# NGNIv1_32.net
KiCad netlist of a schematic drawn in Altium Designer
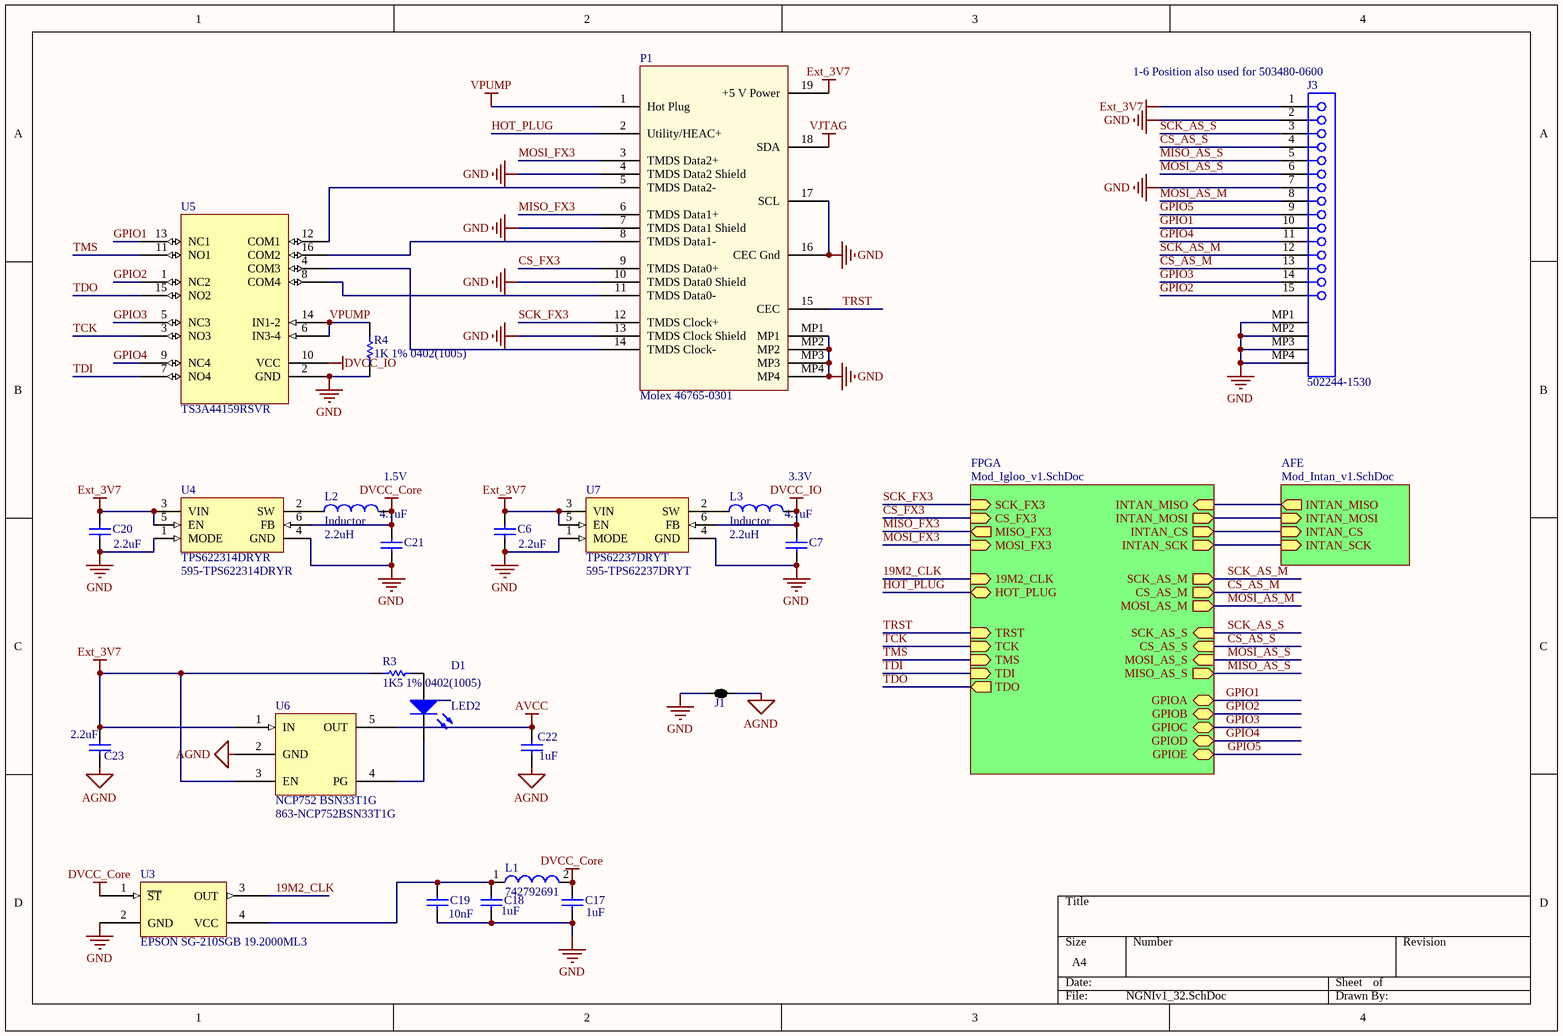
[diagram p0: NGNIv1_32.SchDoc]

(export (version "E")
  (design (tool "Eeschema 10.0.6"))
  (components
    (comp (ref "C6")
      (value "2.2uF")
      (footprint "CAPC0402(1005)60_L")
      (description "CAP 2.2uF 10V Â±20% 0402 (1005 Metric) Thickness 0.6mm SMD")
      (fields (field (name "TOLERANCE") "Â±20%") (field (name "Comment") "CAP 2.2uF 10V 0402(1005)"))
      (libsource (lib "Altium Content Vault") (part "CMP-1034-02128-1"))
    )
    (comp (ref "C7")
      (value "4.7uF")
      (footprint "CAPC0402(1005)60_N")
      (description "CAP 4.7uF 6.3V Â±20% 0402 (1005 Metric) Thickness 0.6mm SMD")
      (fields (field (name "TOLERANCE") "Â±20%") (field (name "Comment") "CAP 4.7uF 6.3V 0402(1005)"))
      (libsource (lib "Altium Content Vault") (part "CMP-1034-02137-1"))
    )
    (comp (ref "C17")
      (value "1uF")
      (footprint "CAPC0402(1005)60_L")
      (description "CAP 1uF 16V Â±10% 0402 (1005 Metric) Thickness 0.6mm SMD")
      (fields (field (name "TOLERANCE") "Â±10%") (field (name "Comment") "CAP 1uF 16V 0402(1005)"))
      (libsource (lib "Altium Content Vault") (part "CMP-1034-02119-1"))
    )
    (comp (ref "C18")
      (value "1uF")
      (footprint "CAPC0402(1005)60_L")
      (description "CAP 1uF 16V Â±20% 0402 (1005 Metric) Thickness 0.6mm SMD")
      (fields (field (name "TOLERANCE") "Â±20%") (field (name "Comment") "CAP 1uF 16V 0402(1005)"))
      (libsource (lib "Altium Content Vault") (part "CMP-1034-02120-1"))
    )
    (comp (ref "C19")
      (value "10nF")
      (footprint "CAPC0402(1005)60_L")
      (description "CAP 10nF 25V ±5% 0402 (1005 Metric) Thickness 0.6mm SMD")
      (fields (field (name "TOLERANCE") "±5%") (field (name "Comment") "CAP 10nF 25V 0402(1005)"))
      (libsource (lib "Altium Content Vault") (part "CMP-1034-01879-1"))
    )
    (comp (ref "C20")
      (value "2.2uF")
      (footprint "CAPC0402(1005)60_L")
      (description "CAP 2.2uF 10V Â±20% 0402 (1005 Metric) Thickness 0.6mm SMD")
      (fields (field (name "TOLERANCE") "Â±20%") (field (name "Comment") "CAP 2.2uF 10V 0402(1005)"))
      (libsource (lib "Altium Content Vault") (part "CMP-1034-02128-1"))
    )
    (comp (ref "C21")
      (value "4.7uF")
      (footprint "CAPC0402(1005)60_N")
      (description "CAP 4.7uF 6.3V Â±20% 0402 (1005 Metric) Thickness 0.6mm SMD")
      (fields (field (name "TOLERANCE") "Â±20%") (field (name "Comment") "CAP 4.7uF 6.3V 0402(1005)"))
      (libsource (lib "Altium Content Vault") (part "CMP-1034-02137-1"))
    )
    (comp (ref "C22")
      (value "1uF")
      (footprint "CAPC0402(1005)60_L")
      (description "CAP 1uF 16V ±10% 0402 (1005 Metric) Thickness 0.6mm SMD")
      (fields (field (name "TOLERANCE") "±10%") (field (name "Comment") "CAP 1uF 16V 0402(1005)"))
      (libsource (lib "Altium Content Vault") (part "CMP-1034-02119-1"))
    )
    (comp (ref "C23")
      (value "2.2uF")
      (footprint "CAPC0603(1608)100_L")
      (description "CAP 2.2uF 25V ±10% 0603 (1608 Metric) Thickness 1mm SMD")
      (fields (field (name "TOLERANCE") "±10%") (field (name "Comment") "CAP 2.2uF 25V 0603(1608)"))
      (libsource (lib "Altium Content Vault") (part "CMP-1035-02767-1"))
    )
    (comp (ref "D1")
      (value "LED2")
      (footprint "LED 0610")
      (description "Typical RED, GREEN, YELLOW, AMBER GaAs LED")
      (fields (field (name "PUBLISHER") "Altium Limited"))
      (libsource (lib "USBridge") (part "LED2"))
    )
    (comp (ref "J1")
      (value "2 way net tie junction")
      (footprint "2way_micro")
      (libsource (lib "NetTie") (part "2way"))
    )
    (comp (ref "J3")
      (value "502244-1530")
      (footprint "MOLX-502244-1530")
      (libsource (lib "USBridge") (part "MOLX-502244-1530"))
    )
    (comp (ref "L1")
      (value "742792691")
      (footprint "SMD-0603")
      (description "SMD EMI Suppression Ferrite Bead WE-CBF, Z = 1500 Ohm")
      (libsource (lib "Altium Content Vault") (part "PAS-IND-INDUCTOR-2"))
    )
    (comp (ref "L2")
      (value "Inductor")
      (footprint "2029")
      (description "LQM21PN2R2")
      (fields (field (name "ALTIUM_VALUE") "2.2uH") (field (name "PUBLISHER") "Altium Limited"))
      (libsource (lib "Miscellaneous Devices") (part "Inductor"))
    )
    (comp (ref "L3")
      (value "Inductor")
      (footprint "2029")
      (description "LQM21PN2R2")
      (fields (field (name "ALTIUM_VALUE") "2.2uH") (field (name "PUBLISHER") "Altium Limited"))
      (libsource (lib "Miscellaneous Devices") (part "Inductor"))
    )
    (comp (ref "P1")
      (value "Molex 46765-0301")
      (footprint "MOLEX 0467650301")
      (description "Micro HDMI")
      (libsource (lib "Schlib1") (part "Molex 46765-0301"))
    )
    (comp (ref "R3")
      (value "1K5 1% 0402(1005)")
      (footprint "RESC0402(1005)_L")
      (description "1K5 0.063W 1% 0402 (1005 Metric)  SMD")
      (fields (field (name "TOLERANCE") "1 %") (field (name "POWER") "0.063 W"))
      (libsource (lib "Altium Content Vault") (part "RES"))
    )
    (comp (ref "R4")
      (value "1K 1% 0402(1005)")
      (footprint "RESC0402(1005)_L")
      (description "1K 0.063W 1% 0402 (1005 Metric)  SMD")
      (fields (field (name "TOLERANCE") "1 %") (field (name "POWER") "0.063 W"))
      (libsource (lib "Altium Content Vault") (part "RES"))
    )
    (comp (ref "U3")
      (value "EPSON SG-210SGB 19.2000ML3")
      (footprint "SG-210S*B")
      (libsource (lib "USBridge") (part "EPSON SG-210SGB 19.2000ML3"))
    )
    (comp (ref "U4")
      (value "TPS622314DRYR")
      (footprint "DRY0006A")
      (description "Voltage Regulators - Switching Regulators 3MHz,500mA Step- Down Converter")
      (fields
        (field (name "PARTNUMBER") "TPS622314DRY")
        (field (name "MANUFACTURER") "Texas Instruments")
        (field (name "SUPPLIER PART NUMBER 1") "595-TPS622314DRYR")
      )
      (libsource (lib "Schlib1") (part "TPS622314DRYR"))
    )
    (comp (ref "U5")
      (value "TS3A44159RSVR")
      (footprint "UQFN-4")
      (description "0.45-Ω Quad SPDT Analog Switch 4-Channel 2:1 Multiplexer – Demultiplexer  With Two Controls")
      (libsource (lib "USBridge") (part "TS3A44159RSVR"))
    )
    (comp (ref "U6")
      (value "NCP752 BSN33T1G")
      (footprint "TSOP5 NCP752")
      (description "3.3V LDO 200ma ultra low quiescent current, ultra low noise")
      (fields (field (name "SUPPLIER PART NUMBER 1") "863-NCP752BSN33T1G"))
      (libsource (lib "Schlib1") (part "NCP752 BSN33T1G"))
    )
    (comp (ref "U7")
      (value "TPS62237DRYT")
      (footprint "DRY0006A")
      (description "Voltage Regulators - Switching Regulators 3MHz,500mA Step- Down Converter")
      (fields
        (field (name "PARTNUMBER") "TPS622314DRY")
        (field (name "MANUFACTURER") "Texas Instruments")
        (field (name "SUPPLIER PART NUMBER 1") "595-TPS62237DRYT")
      )
      (libsource (lib "USBridge") (part "TPS62237DRYT"))
    )
  )
  (nets
    (net (code "1") (name "/19M2_CLK") (class "Default")
      (node (ref "U3") (pin "3") (pinfunction "OUT_3") (pintype "output"))
    )
    (net (code "2") (name "/CS_AS_M") (class "Default")
      (node (ref "J3") (pin "13") (pinfunction "13_13") (pintype "passive"))
    )
    (net (code "3") (name "/CS_AS_S") (class "Default")
      (node (ref "J3") (pin "4") (pinfunction "4_4") (pintype "passive"))
    )
    (net (code "4") (name "/CS_FX3") (class "Default")
      (node (ref "P1") (pin "9") (pinfunction "TMDS_Data0+_9") (pintype "passive"))
    )
    (net (code "5") (name "/GPIO1") (class "Default")
      (node (ref "J3") (pin "10") (pinfunction "10_10") (pintype "passive"))
      (node (ref "U5") (pin "13") (pinfunction "NC1_13") (pintype "bidirectional"))
    )
    (net (code "6") (name "/GPIO2") (class "Default")
      (node (ref "J3") (pin "15") (pinfunction "15_15") (pintype "passive"))
      (node (ref "U5") (pin "1") (pinfunction "NC2_1") (pintype "bidirectional"))
    )
    (net (code "7") (name "/GPIO3") (class "Default")
      (node (ref "J3") (pin "14") (pinfunction "14_14") (pintype "passive"))
      (node (ref "U5") (pin "5") (pinfunction "NC3_5") (pintype "bidirectional"))
    )
    (net (code "8") (name "/GPIO4") (class "Default")
      (node (ref "J3") (pin "11") (pinfunction "11_11") (pintype "passive"))
      (node (ref "U5") (pin "9") (pinfunction "NC4_9") (pintype "bidirectional"))
    )
    (net (code "9") (name "/GPIO5") (class "Default")
      (node (ref "J3") (pin "9") (pinfunction "9_9") (pintype "passive"))
    )
    (net (code "10") (name "/HOT_PLUG") (class "Default")
      (node (ref "P1") (pin "2") (pinfunction "Utility/HEAC+_2") (pintype "passive"))
    )
    (net (code "15") (name "/MISO_AS_S") (class "Default")
      (node (ref "J3") (pin "5") (pinfunction "5_5") (pintype "passive"))
    )
    (net (code "16") (name "/MISO_FX3") (class "Default")
      (node (ref "P1") (pin "6") (pinfunction "TMDS_Data1+_6") (pintype "passive"))
    )
    (net (code "17") (name "/MOSI_AS_M") (class "Default")
      (node (ref "J3") (pin "8") (pinfunction "8_8") (pintype "passive"))
    )
    (net (code "18") (name "/MOSI_AS_S") (class "Default")
      (node (ref "J3") (pin "6") (pinfunction "6_6") (pintype "passive"))
    )
    (net (code "19") (name "/MOSI_FX3") (class "Default")
      (node (ref "P1") (pin "3") (pinfunction "TMDS_Data2+_3") (pintype "passive"))
    )
    (net (code "20") (name "/SCK_AS_M") (class "Default")
      (node (ref "J3") (pin "12") (pinfunction "12_12") (pintype "passive"))
    )
    (net (code "21") (name "/SCK_AS_S") (class "Default")
      (node (ref "J3") (pin "3") (pinfunction "3_3") (pintype "passive"))
    )
    (net (code "22") (name "/SCK_FX3") (class "Default")
      (node (ref "P1") (pin "12") (pinfunction "TMDS_Clock+_12") (pintype "passive"))
    )
    (net (code "23") (name "/TCK") (class "Default")
      (node (ref "U5") (pin "3") (pinfunction "NO3_3") (pintype "bidirectional"))
    )
    (net (code "24") (name "/TDI") (class "Default")
      (node (ref "U5") (pin "7") (pinfunction "NO4_7") (pintype "bidirectional"))
    )
    (net (code "25") (name "/TDO") (class "Default")
      (node (ref "U5") (pin "15") (pinfunction "NO2_15") (pintype "bidirectional"))
    )
    (net (code "26") (name "/TMS") (class "Default")
      (node (ref "U5") (pin "11") (pinfunction "NO1_11") (pintype "bidirectional"))
    )
    (net (code "27") (name "/TRST") (class "Default")
      (node (ref "P1") (pin "15") (pinfunction "CEC_15") (pintype "passive"))
    )
    (net (code "28") (name "AGND") (class "Default")
      (node (ref "C22") (pin "1") (pinfunction "1_1") (pintype "passive"))
      (node (ref "C23") (pin "1") (pinfunction "1_1") (pintype "passive"))
      (node (ref "J1") (pin "2") (pinfunction "2_2") (pintype "passive"))
      (node (ref "U6") (pin "2") (pinfunction "GND_2") (pintype "passive"))
    )
    (net (code "29") (name "AVCC") (class "Default")
      (node (ref "C22") (pin "2") (pinfunction "2_2") (pintype "passive"))
      (node (ref "U6") (pin "5") (pinfunction "OUT_5") (pintype "passive"))
    )
    (net (code "30") (name "DVCC_Core") (class "Default")
      (node (ref "C17") (pin "2") (pinfunction "2_2") (pintype "passive"))
      (node (ref "C21") (pin "1") (pinfunction "1_1") (pintype "passive"))
      (node (ref "L1") (pin "2") (pinfunction "2_2") (pintype "passive"))
      (node (ref "L2") (pin "2") (pinfunction "2_2") (pintype "passive"))
      (node (ref "U3") (pin "1") (pinfunction "~{ST}_1") (pintype "input"))
      (node (ref "U4") (pin "6") (pinfunction "FB_6") (pintype "input"))
    )
    (net (code "31") (name "DVCC_IO") (class "Default")
      (node (ref "C7") (pin "1") (pinfunction "1_1") (pintype "passive"))
      (node (ref "L3") (pin "2") (pinfunction "2_2") (pintype "passive"))
      (node (ref "U5") (pin "10") (pinfunction "VCC_10") (pintype "power_in"))
      (node (ref "U7") (pin "6") (pinfunction "FB_6") (pintype "input"))
    )
    (net (code "32") (name "Ext_3V7") (class "Default")
      (node (ref "C20") (pin "2") (pinfunction "2_2") (pintype "passive"))
      (node (ref "C23") (pin "2") (pinfunction "2_2") (pintype "passive"))
      (node (ref "C6") (pin "2") (pinfunction "2_2") (pintype "passive"))
      (node (ref "J3") (pin "1") (pinfunction "1_1") (pintype "passive"))
      (node (ref "P1") (pin "19") (pinfunction "+5_V_Power_19") (pintype "passive"))
      (node (ref "R3") (pin "1") (pinfunction "1_1") (pintype "passive"))
      (node (ref "U4") (pin "3") (pinfunction "VIN_3") (pintype "power_in"))
      (node (ref "U4") (pin "5") (pinfunction "EN_5") (pintype "input"))
      (node (ref "U6") (pin "1") (pinfunction "IN_1") (pintype "input"))
      (node (ref "U6") (pin "3") (pinfunction "EN_3") (pintype "passive"))
      (node (ref "U7") (pin "3") (pinfunction "VIN_3") (pintype "power_in"))
      (node (ref "U7") (pin "5") (pinfunction "EN_5") (pintype "input"))
    )
    (net (code "33") (name "GND") (class "Default")
      (node (ref "C17") (pin "1") (pinfunction "1_1") (pintype "passive"))
      (node (ref "C18") (pin "1") (pinfunction "1_1") (pintype "passive"))
      (node (ref "C19") (pin "1") (pinfunction "1_1") (pintype "passive"))
      (node (ref "C20") (pin "1") (pinfunction "1_1") (pintype "passive"))
      (node (ref "C21") (pin "2") (pinfunction "2_2") (pintype "passive"))
      (node (ref "C6") (pin "1") (pinfunction "1_1") (pintype "passive"))
      (node (ref "C7") (pin "2") (pinfunction "2_2") (pintype "passive"))
      (node (ref "J1") (pin "1") (pinfunction "1_1") (pintype "passive"))
      (node (ref "J3") (pin "2") (pinfunction "2_2") (pintype "passive"))
      (node (ref "J3") (pin "7") (pinfunction "7_7") (pintype "passive"))
      (node (ref "J3") (pin "MP1") (pinfunction "MP1_MP1") (pintype "passive"))
      (node (ref "J3") (pin "MP2") (pinfunction "MP2_MP2") (pintype "passive"))
      (node (ref "J3") (pin "MP3") (pinfunction "MP3_MP3") (pintype "passive"))
      (node (ref "J3") (pin "MP4") (pinfunction "MP4_MP4") (pintype "passive"))
      (node (ref "P1") (pin "10") (pinfunction "TMDS_Data0_Shield_10") (pintype "passive"))
      (node (ref "P1") (pin "13") (pinfunction "TMDS_Clock_Shield_13") (pintype "passive"))
      (node (ref "P1") (pin "16") (pinfunction "CEC_Gnd_16") (pintype "passive"))
      (node (ref "P1") (pin "17") (pinfunction "SCL_17") (pintype "passive"))
      (node (ref "P1") (pin "4") (pinfunction "TMDS_Data2_Shield_4") (pintype "passive"))
      (node (ref "P1") (pin "7") (pinfunction "TMDS_Data1_Shield_7") (pintype "passive"))
      (node (ref "P1") (pin "MP1") (pinfunction "MP1_MP1") (pintype "passive"))
      (node (ref "P1") (pin "MP2") (pinfunction "MP2_MP2") (pintype "passive"))
      (node (ref "P1") (pin "MP3") (pinfunction "MP3_MP3") (pintype "passive"))
      (node (ref "P1") (pin "MP4") (pinfunction "MP4_MP4") (pintype "passive"))
      (node (ref "R4") (pin "2") (pinfunction "2_2") (pintype "passive"))
      (node (ref "U3") (pin "2") (pinfunction "GND_2") (pintype "power_in"))
      (node (ref "U4") (pin "1") (pinfunction "MODE_1") (pintype "input"))
      (node (ref "U4") (pin "4") (pinfunction "GND_4") (pintype "power_in"))
      (node (ref "U5") (pin "2") (pinfunction "GND_2") (pintype "power_in"))
      (node (ref "U7") (pin "1") (pinfunction "MODE_1") (pintype "input"))
      (node (ref "U7") (pin "4") (pinfunction "GND_4") (pintype "power_in"))
    )
    (net (code "34") (name "Net-(D1-A)") (class "Default")
      (node (ref "D1") (pin "1") (pinfunction "A_1") (pintype "passive"))
      (node (ref "R3") (pin "2") (pinfunction "2_2") (pintype "passive"))
    )
    (net (code "35") (name "Net-(D1-K)") (class "Default")
      (node (ref "D1") (pin "2") (pinfunction "K_2") (pintype "passive"))
      (node (ref "U6") (pin "4") (pinfunction "PG_4") (pintype "passive"))
    )
    (net (code "36") (name "Net-(P1-TMDS_Clock-)") (class "Default")
      (node (ref "P1") (pin "14") (pinfunction "TMDS_Clock-_14") (pintype "passive"))
      (node (ref "U5") (pin "4") (pinfunction "COM3_4") (pintype "bidirectional"))
    )
    (net (code "37") (name "Net-(P1-TMDS_Data0-)") (class "Default")
      (node (ref "P1") (pin "11") (pinfunction "TMDS_Data0-_11") (pintype "passive"))
      (node (ref "U5") (pin "8") (pinfunction "COM4_8") (pintype "bidirectional"))
    )
    (net (code "38") (name "Net-(P1-TMDS_Data1-)") (class "Default")
      (node (ref "P1") (pin "8") (pinfunction "TMDS_Data1-_8") (pintype "passive"))
      (node (ref "U5") (pin "16") (pinfunction "COM2_16") (pintype "bidirectional"))
    )
    (net (code "39") (name "Net-(P1-TMDS_Data2-)") (class "Default")
      (node (ref "P1") (pin "5") (pinfunction "TMDS_Data2-_5") (pintype "passive"))
      (node (ref "U5") (pin "12") (pinfunction "COM1_12") (pintype "bidirectional"))
    )
    (net (code "40") (name "Net-(U3-VCC)") (class "Default")
      (node (ref "C18") (pin "2") (pinfunction "2_2") (pintype "passive"))
      (node (ref "C19") (pin "2") (pinfunction "2_2") (pintype "passive"))
      (node (ref "L1") (pin "1") (pinfunction "1_1") (pintype "passive"))
      (node (ref "U3") (pin "4") (pinfunction "VCC_4") (pintype "power_in"))
    )
    (net (code "41") (name "Net-(U4-SW)") (class "Default")
      (node (ref "L2") (pin "1") (pinfunction "1_1") (pintype "passive"))
      (node (ref "U4") (pin "2") (pinfunction "SW_2") (pintype "power_in"))
    )
    (net (code "42") (name "Net-(U7-SW)") (class "Default")
      (node (ref "L3") (pin "1") (pinfunction "1_1") (pintype "passive"))
      (node (ref "U7") (pin "2") (pinfunction "SW_2") (pintype "power_in"))
    )
    (net (code "43") (name "VJTAG") (class "Default")
      (node (ref "P1") (pin "18") (pinfunction "SDA_18") (pintype "passive"))
    )
    (net (code "44") (name "VPUMP") (class "Default")
      (node (ref "P1") (pin "1") (pinfunction "Hot_Plug_1") (pintype "passive"))
      (node (ref "R4") (pin "1") (pinfunction "1_1") (pintype "passive"))
      (node (ref "U5") (pin "14") (pinfunction "IN1-2_14") (pintype "input"))
      (node (ref "U5") (pin "6") (pinfunction "IN3-4_6") (pintype "input"))
    )
  )
)
